# Regulator3V3.net
KiCad netlist of a schematic drawn in Altium Designer
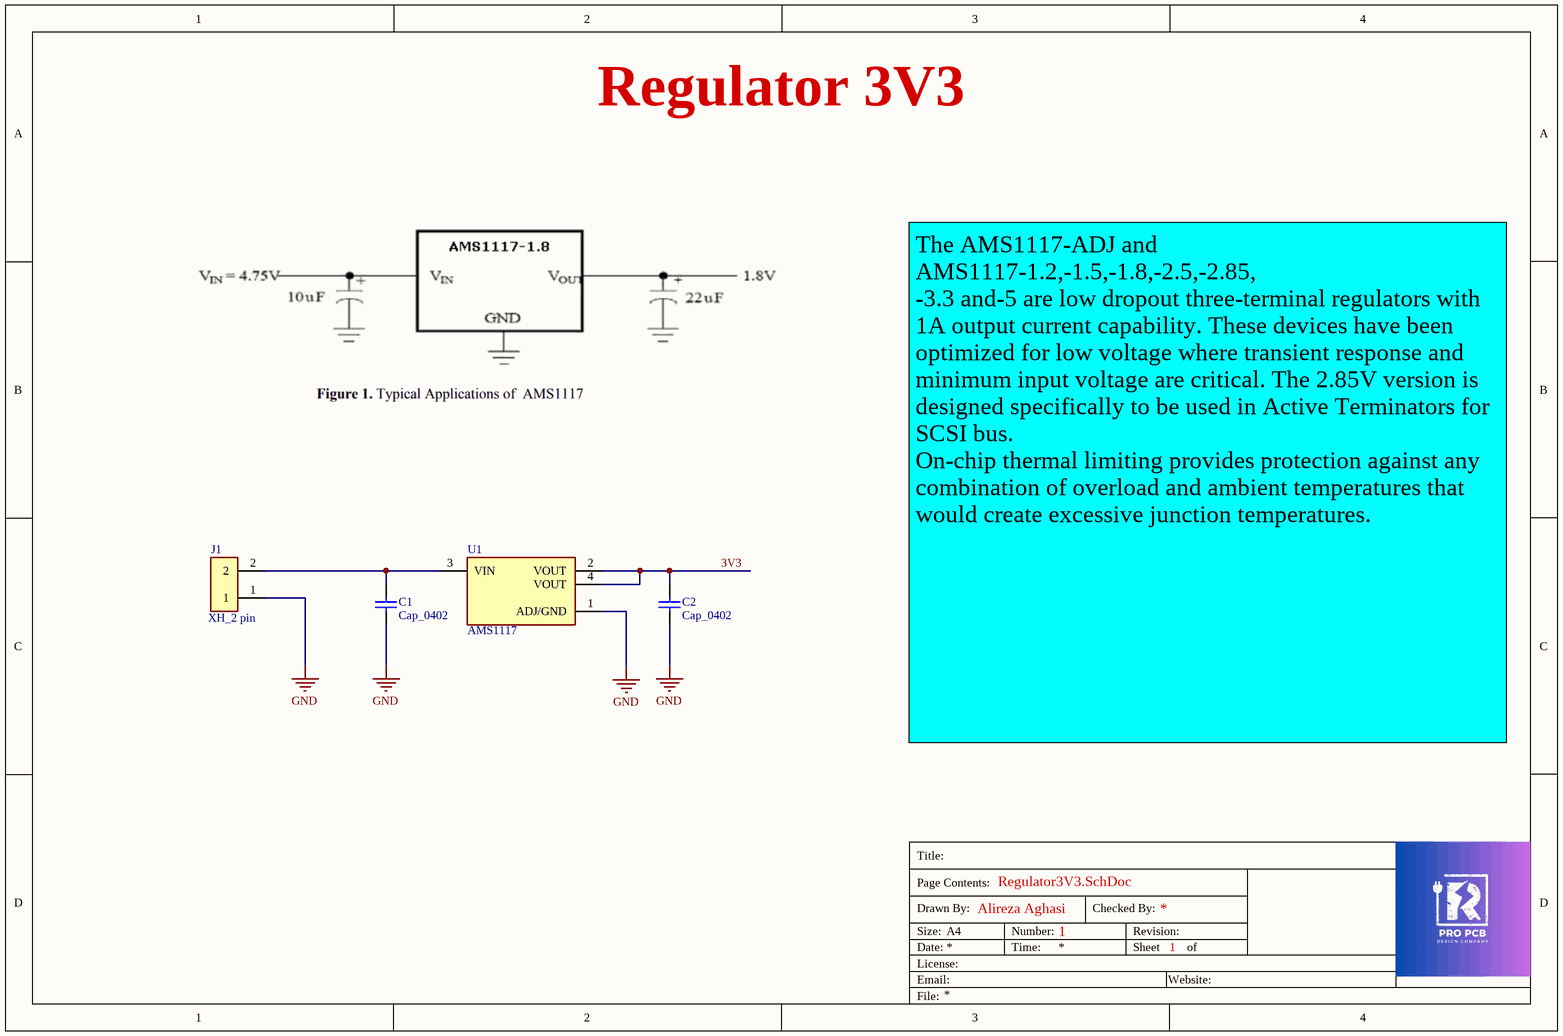
[diagram p0: Regulator3V3.SchDoc]

(export (version "E")
  (design (tool "Eeschema 10.0.6"))
  (components
    (comp (ref "C1")
      (value "Cap_0402")
      (footprint "Capacitor_0603")
      (description "0402")
      (fields (field (name "PUBLISHER") "Altium Limited"))
      (libsource (lib "Control Boad LIBS") (part "Cap_0402"))
    )
    (comp (ref "C2")
      (value "Cap_0402")
      (footprint "Capacitor_0603")
      (description "0402")
      (fields (field (name "PUBLISHER") "Altium Limited"))
      (libsource (lib "Control Boad LIBS") (part "Cap_0402"))
    )
    (comp (ref "J1")
      (value "XH_2 pin")
      (footprint "JST_S2B-XH-A(LF)(SN)")
      (description "2 Position Wire to Board Terminal Block Horizontal with Board 0.197 (5.00mm) Through Hole")
      (fields (field (name "MF") "Phoenix Contact") (field (name "MP") "1935161"))
      (libsource (lib "Control Boad LIBS") (part "PHOENIX_2 pin"))
    )
    (comp (ref "U1")
      (value "AMS1117")
      (footprint "SOT229P700X180-4N")
      (description "1A LOW DROPOUT VOLTAGE REGULATOR SOT-223")
      (fields (field (name "MF") "Advanced Monolithic Systems"))
      (libsource (lib "PROPCB") (part "AMS1117"))
    )
  )
  (nets
    (net (code "1") (name "/3V3") (class "Default")
      (node (ref "C2") (pin "2") (pinfunction "2_2") (pintype "passive"))
      (node (ref "U1") (pin "2") (pinfunction "VOUT_2") (pintype "passive"))
      (node (ref "U1") (pin "4") (pinfunction "VOUT_4") (pintype "passive"))
    )
    (net (code "2") (name "GND") (class "Default")
      (node (ref "C1") (pin "1") (pinfunction "1_1") (pintype "passive"))
      (node (ref "C2") (pin "1") (pinfunction "1_1") (pintype "passive"))
      (node (ref "J1") (pin "1") (pinfunction "1_1") (pintype "passive"))
      (node (ref "U1") (pin "1") (pinfunction "ADJ/GND_1") (pintype "power_in"))
    )
    (net (code "3") (name "Net-(U1-VIN)") (class "Default")
      (node (ref "C1") (pin "2") (pinfunction "2_2") (pintype "passive"))
      (node (ref "J1") (pin "2") (pinfunction "2_2") (pintype "passive"))
      (node (ref "U1") (pin "3") (pinfunction "VIN_3") (pintype "passive"))
    )
  )
)
